# pc_afe4400_shield.net
KiCad netlist of a schematic drawn in EAGLE
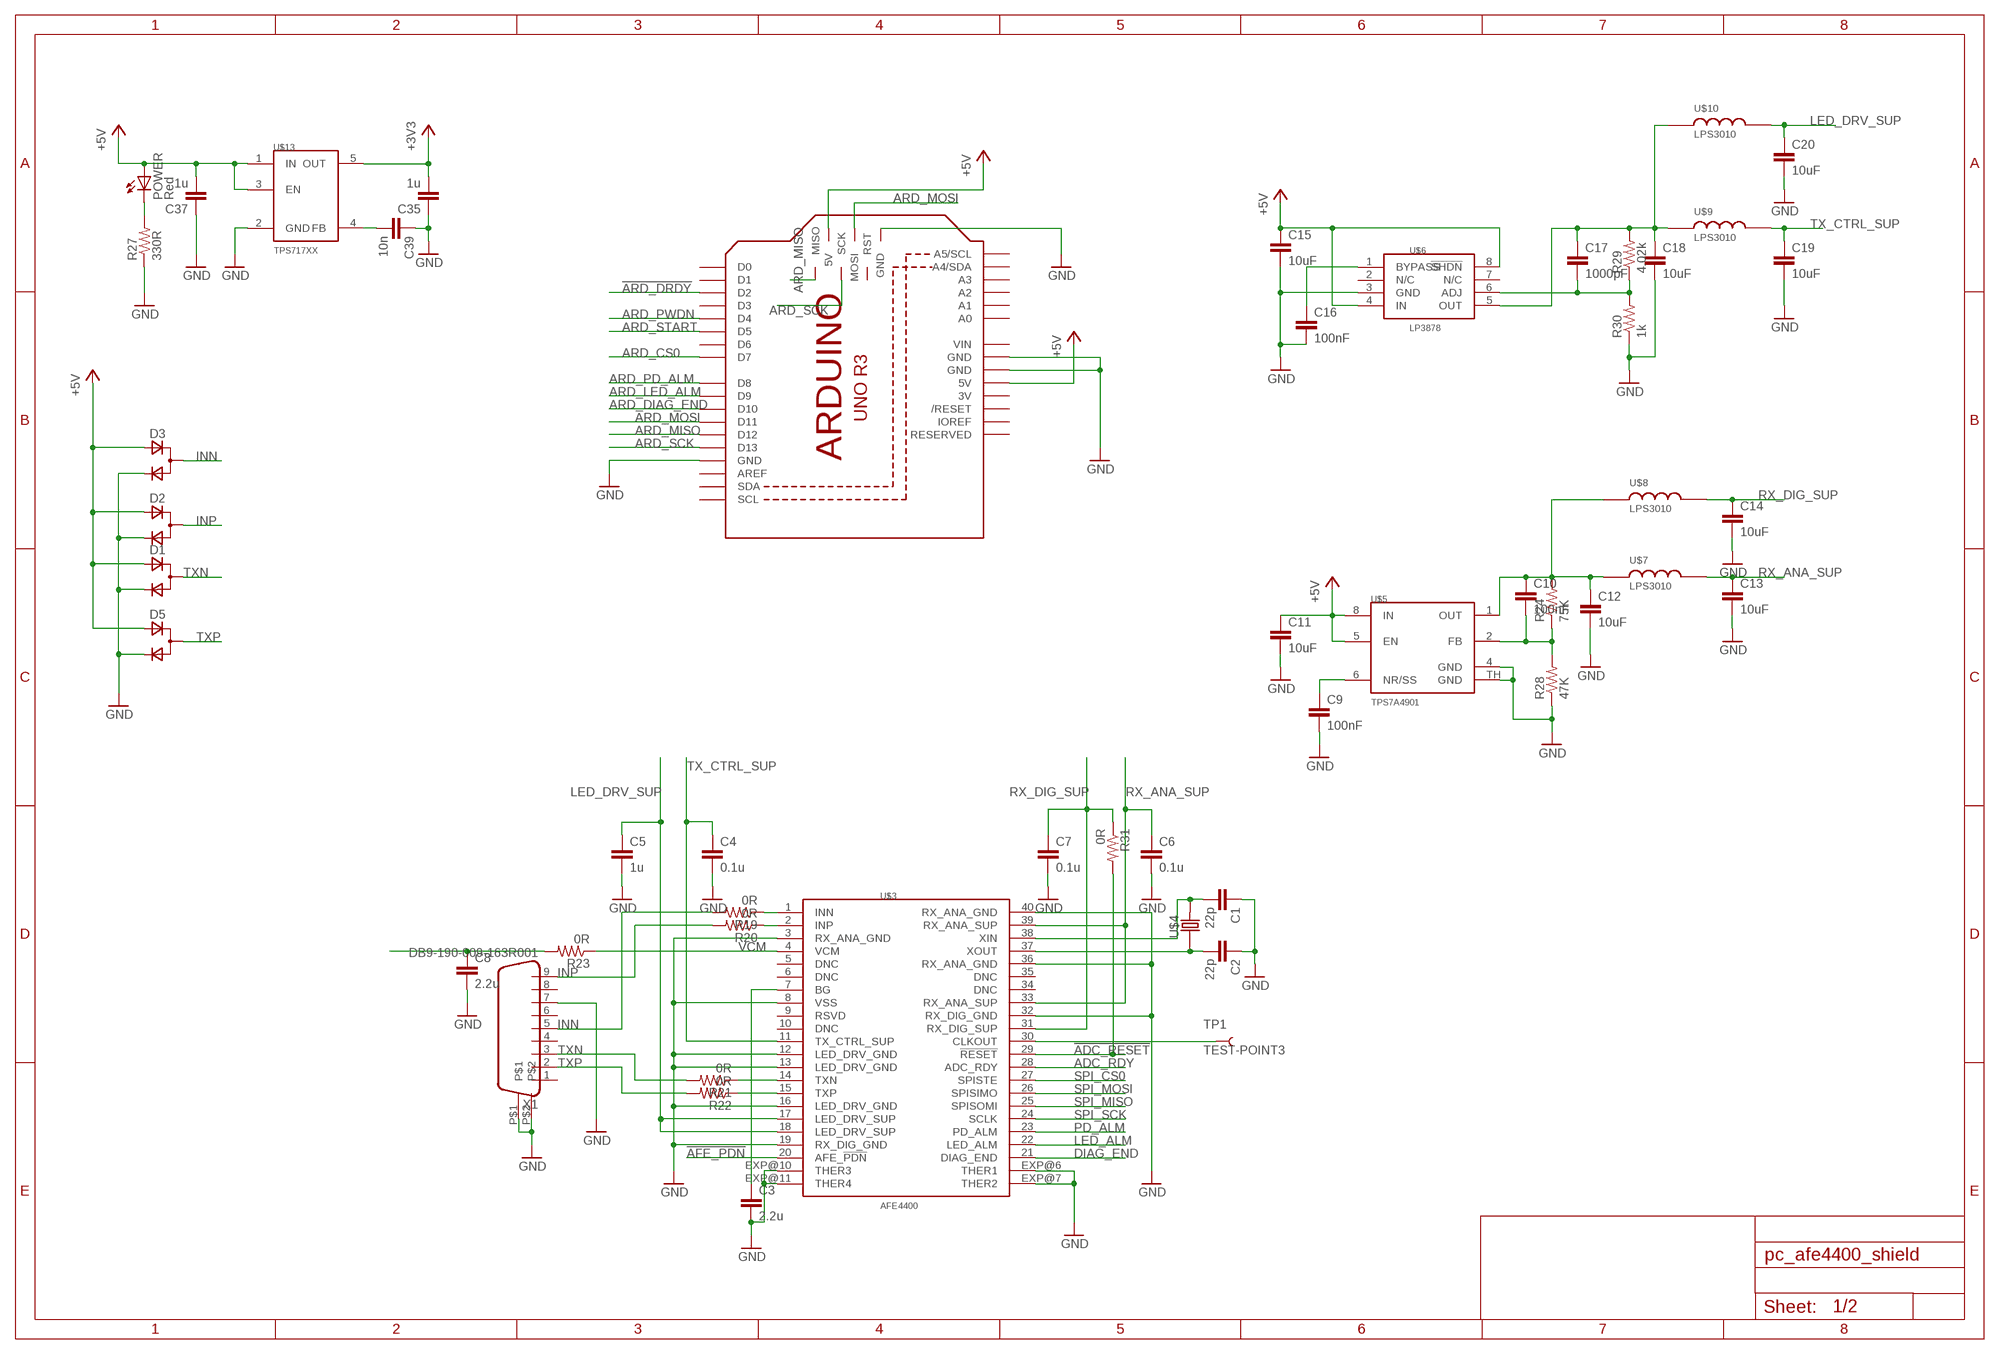
[diagram p0: schematic, sheet 1]
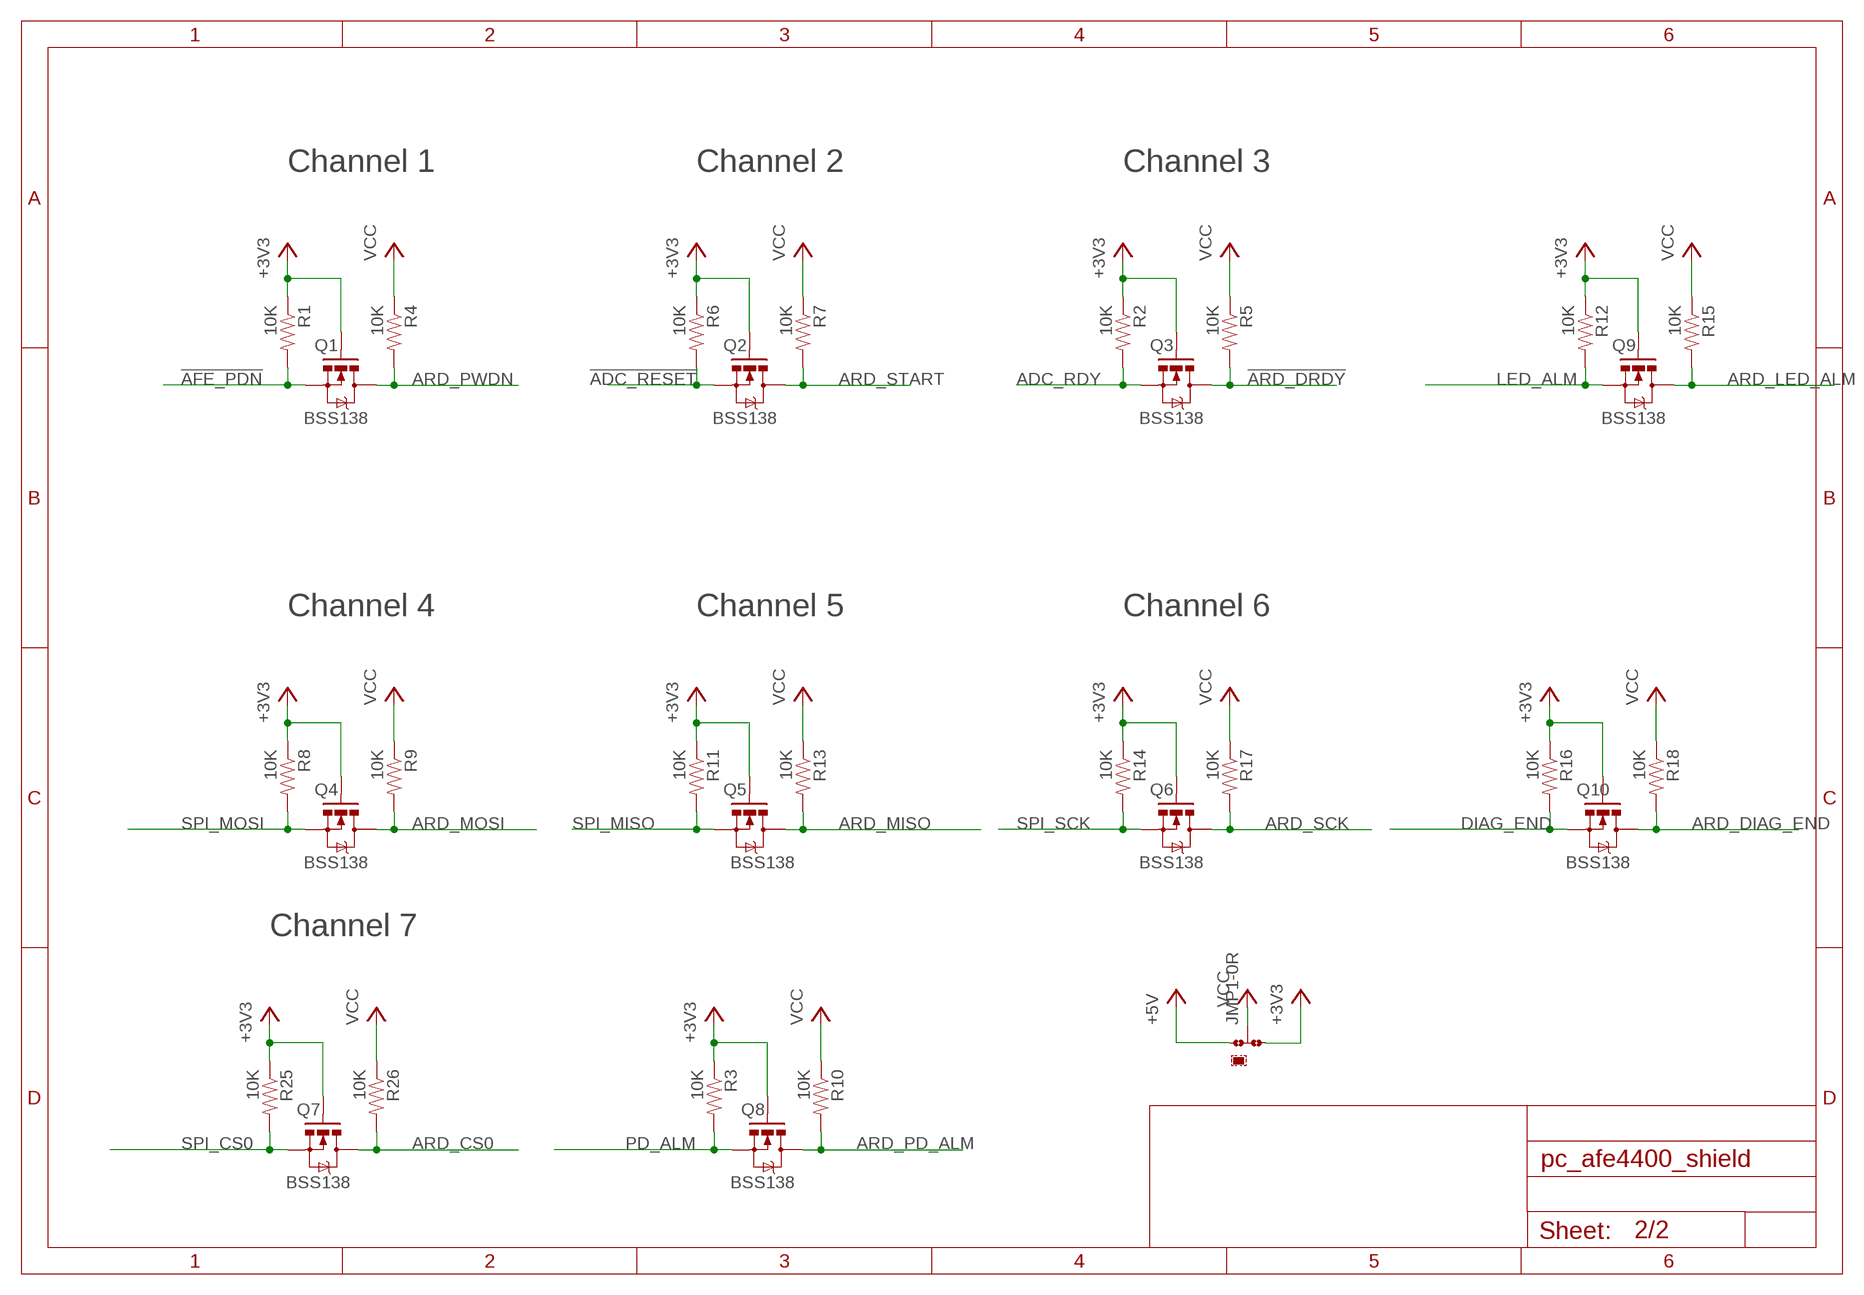
[diagram p1: schematic, sheet 2]

(export (version "E")
  (design (tool "Eeschema 10.0.6"))
  (components
    (comp (ref "JMP1")
      (value "0R-JUMPA")
      (footprint "eagle-import:A0R-JMP")
      (libsource (lib "eagle-import") (part "0R-JUMPA"))
    )
    (comp (ref "Q1")
      (value "BSS138")
      (footprint "eagle-import:SOT23-3")
      (libsource (lib "eagle-import") (part "MOSFET-NCHANNELSMD"))
    )
    (comp (ref "Q2")
      (value "BSS138")
      (footprint "eagle-import:SOT23-3")
      (libsource (lib "eagle-import") (part "MOSFET-NCHANNELSMD"))
    )
    (comp (ref "Q3")
      (value "BSS138")
      (footprint "eagle-import:SOT23-3")
      (libsource (lib "eagle-import") (part "MOSFET-NCHANNELSMD"))
    )
    (comp (ref "Q4")
      (value "BSS138")
      (footprint "eagle-import:SOT23-3")
      (libsource (lib "eagle-import") (part "MOSFET-NCHANNELSMD"))
    )
    (comp (ref "Q5")
      (value "BSS138")
      (footprint "eagle-import:SOT23-3")
      (libsource (lib "eagle-import") (part "MOSFET-NCHANNELSMD"))
    )
    (comp (ref "Q6")
      (value "BSS138")
      (footprint "eagle-import:SOT23-3")
      (libsource (lib "eagle-import") (part "MOSFET-NCHANNELSMD"))
    )
    (comp (ref "Q7")
      (value "BSS138")
      (footprint "eagle-import:SOT23-3")
      (libsource (lib "eagle-import") (part "MOSFET-NCHANNELSMD"))
    )
    (comp (ref "Q8")
      (value "BSS138")
      (footprint "eagle-import:SOT23-3")
      (libsource (lib "eagle-import") (part "MOSFET-NCHANNELSMD"))
    )
    (comp (ref "Q9")
      (value "BSS138")
      (footprint "eagle-import:SOT23-3")
      (libsource (lib "eagle-import") (part "MOSFET-NCHANNELSMD"))
    )
    (comp (ref "Q10")
      (value "BSS138")
      (footprint "eagle-import:SOT23-3")
      (libsource (lib "eagle-import") (part "MOSFET-NCHANNELSMD"))
    )
    (comp (ref "R1")
      (value "10K")
      (footprint "eagle-import:0805")
      (libsource (lib "eagle-import") (part "RESISTOR0805-RES"))
    )
    (comp (ref "R2")
      (value "10K")
      (footprint "eagle-import:0805")
      (libsource (lib "eagle-import") (part "RESISTOR0805-RES"))
    )
    (comp (ref "R3")
      (value "10K")
      (footprint "eagle-import:0805")
      (libsource (lib "eagle-import") (part "RESISTOR0805-RES"))
    )
    (comp (ref "R4")
      (value "10K")
      (footprint "eagle-import:0805")
      (libsource (lib "eagle-import") (part "RESISTOR0805-RES"))
    )
    (comp (ref "R5")
      (value "10K")
      (footprint "eagle-import:0805")
      (libsource (lib "eagle-import") (part "RESISTOR0805-RES"))
    )
    (comp (ref "R6")
      (value "10K")
      (footprint "eagle-import:0805")
      (libsource (lib "eagle-import") (part "RESISTOR0805-RES"))
    )
    (comp (ref "R7")
      (value "10K")
      (footprint "eagle-import:0805")
      (libsource (lib "eagle-import") (part "RESISTOR0805-RES"))
    )
    (comp (ref "R8")
      (value "10K")
      (footprint "eagle-import:0805")
      (libsource (lib "eagle-import") (part "RESISTOR0805-RES"))
    )
    (comp (ref "R9")
      (value "10K")
      (footprint "eagle-import:0805")
      (libsource (lib "eagle-import") (part "RESISTOR0805-RES"))
    )
    (comp (ref "R10")
      (value "10K")
      (footprint "eagle-import:0805")
      (libsource (lib "eagle-import") (part "RESISTOR0805-RES"))
    )
    (comp (ref "R11")
      (value "10K")
      (footprint "eagle-import:0805")
      (libsource (lib "eagle-import") (part "RESISTOR0805-RES"))
    )
    (comp (ref "R12")
      (value "10K")
      (footprint "eagle-import:0805")
      (libsource (lib "eagle-import") (part "RESISTOR0805-RES"))
    )
    (comp (ref "R13")
      (value "10K")
      (footprint "eagle-import:0805")
      (libsource (lib "eagle-import") (part "RESISTOR0805-RES"))
    )
    (comp (ref "R14")
      (value "10K")
      (footprint "eagle-import:0805")
      (libsource (lib "eagle-import") (part "RESISTOR0805-RES"))
    )
    (comp (ref "R15")
      (value "10K")
      (footprint "eagle-import:0805")
      (libsource (lib "eagle-import") (part "RESISTOR0805-RES"))
    )
    (comp (ref "R16")
      (value "10K")
      (footprint "eagle-import:0805")
      (libsource (lib "eagle-import") (part "RESISTOR0805-RES"))
    )
    (comp (ref "R17")
      (value "10K")
      (footprint "eagle-import:0805")
      (libsource (lib "eagle-import") (part "RESISTOR0805-RES"))
    )
    (comp (ref "R18")
      (value "10K")
      (footprint "eagle-import:0805")
      (libsource (lib "eagle-import") (part "RESISTOR0805-RES"))
    )
    (comp (ref "R25")
      (value "10K")
      (footprint "eagle-import:0805")
      (libsource (lib "eagle-import") (part "RESISTOR0805-RES"))
    )
    (comp (ref "R26")
      (value "10K")
      (footprint "eagle-import:0805")
      (libsource (lib "eagle-import") (part "RESISTOR0805-RES"))
    )
    (comp (ref "C1")
      (value "22p")
      (footprint "eagle-import:C0402")
      (libsource (lib "eagle-import") (part "C-EUC0402"))
    )
    (comp (ref "C2")
      (value "22p")
      (footprint "eagle-import:C0402")
      (libsource (lib "eagle-import") (part "C-EUC0402"))
    )
    (comp (ref "C3")
      (value "2.2u")
      (footprint "eagle-import:C0402")
      (libsource (lib "eagle-import") (part "C-EUC0402"))
    )
    (comp (ref "C4")
      (value "0.1u")
      (footprint "eagle-import:C0805")
      (libsource (lib "eagle-import") (part "C-EUC0805"))
    )
    (comp (ref "C5")
      (value "1u")
      (footprint "eagle-import:C0805")
      (libsource (lib "eagle-import") (part "C-EUC0805"))
    )
    (comp (ref "C6")
      (value "0.1u")
      (footprint "eagle-import:C0805")
      (libsource (lib "eagle-import") (part "C-EUC0805"))
    )
    (comp (ref "C7")
      (value "0.1u")
      (footprint "eagle-import:C0805")
      (libsource (lib "eagle-import") (part "C-EUC0805"))
    )
    (comp (ref "C8")
      (value "2.2u")
      (footprint "eagle-import:C0402")
      (libsource (lib "eagle-import") (part "C-EUC0402"))
    )
    (comp (ref "C9")
      (value "100nF")
      (footprint "eagle-import:C0805")
      (libsource (lib "eagle-import") (part "C-EUC0805"))
    )
    (comp (ref "C10")
      (value "100nF")
      (footprint "eagle-import:C0805")
      (libsource (lib "eagle-import") (part "C-EUC0805"))
    )
    (comp (ref "C11")
      (value "10uF")
      (footprint "eagle-import:C0805")
      (libsource (lib "eagle-import") (part "C-EUC0805"))
    )
    (comp (ref "C12")
      (value "10uF")
      (footprint "eagle-import:C0805")
      (libsource (lib "eagle-import") (part "C-EUC0805"))
    )
    (comp (ref "C13")
      (value "10uF")
      (footprint "eagle-import:C0805")
      (libsource (lib "eagle-import") (part "C-EUC0805"))
    )
    (comp (ref "C14")
      (value "10uF")
      (footprint "eagle-import:C0805")
      (libsource (lib "eagle-import") (part "C-EUC0805"))
    )
    (comp (ref "C15")
      (value "10uF")
      (footprint "eagle-import:C0805")
      (libsource (lib "eagle-import") (part "C-EUC0805"))
    )
    (comp (ref "C16")
      (value "100nF")
      (footprint "eagle-import:C0805")
      (libsource (lib "eagle-import") (part "C-EUC0805"))
    )
    (comp (ref "C17")
      (value "1000pF")
      (footprint "eagle-import:C0805")
      (libsource (lib "eagle-import") (part "C-EUC0805"))
    )
    (comp (ref "C18")
      (value "10uF")
      (footprint "eagle-import:C0805")
      (libsource (lib "eagle-import") (part "C-EUC0805"))
    )
    (comp (ref "C19")
      (value "10uF")
      (footprint "eagle-import:C0805")
      (libsource (lib "eagle-import") (part "C-EUC0805"))
    )
    (comp (ref "C20")
      (value "10uF")
      (footprint "eagle-import:C0805")
      (libsource (lib "eagle-import") (part "C-EUC0805"))
    )
    (comp (ref "C35")
      (value "1u")
      (footprint "eagle-import:C0805")
      (libsource (lib "eagle-import") (part "C-EUC0805"))
    )
    (comp (ref "C37")
      (value "1u")
      (footprint "eagle-import:C0805")
      (libsource (lib "eagle-import") (part "C-EUC0805"))
    )
    (comp (ref "C39")
      (value "10n")
      (footprint "eagle-import:C0805")
      (libsource (lib "eagle-import") (part "C-EUC0805"))
    )
    (comp (ref "D1")
      (value "D_ACACSOT323")
      (footprint "eagle-import:SOT323")
      (libsource (lib "eagle-import") (part "D_ACACSOT323"))
    )
    (comp (ref "D2")
      (value "D_ACACSOT323")
      (footprint "eagle-import:SOT323")
      (libsource (lib "eagle-import") (part "D_ACACSOT323"))
    )
    (comp (ref "D3")
      (value "D_ACACSOT323")
      (footprint "eagle-import:SOT323")
      (libsource (lib "eagle-import") (part "D_ACACSOT323"))
    )
    (comp (ref "D5")
      (value "D_ACACSOT323")
      (footprint "eagle-import:SOT323")
      (libsource (lib "eagle-import") (part "D_ACACSOT323"))
    )
    (comp (ref "M1")
      (value "ARDUINO")
      (footprint "eagle-import:ARDUINO")
      (libsource (lib "eagle-import") (part "ARDUINO"))
    )
    (comp (ref "POWER")
      (value "Red")
      (footprint "eagle-import:CHIPLED_0603")
      (libsource (lib "eagle-import") (part "LEDCHIPLED_0603"))
    )
    (comp (ref "R19")
      (value "0R")
      (footprint "eagle-import:R0402")
      (libsource (lib "eagle-import") (part "R-US_R0402"))
    )
    (comp (ref "R20")
      (value "0R")
      (footprint "eagle-import:R0402")
      (libsource (lib "eagle-import") (part "R-US_R0402"))
    )
    (comp (ref "R21")
      (value "0R")
      (footprint "eagle-import:R0805")
      (libsource (lib "eagle-import") (part "R-US_R0805"))
    )
    (comp (ref "R22")
      (value "0R")
      (footprint "eagle-import:R0805")
      (libsource (lib "eagle-import") (part "R-US_R0805"))
    )
    (comp (ref "R23")
      (value "0R")
      (footprint "eagle-import:R0402")
      (libsource (lib "eagle-import") (part "R-US_R0402"))
    )
    (comp (ref "R24")
      (value "75K")
      (footprint "eagle-import:R0805")
      (libsource (lib "eagle-import") (part "R-US_R0805"))
    )
    (comp (ref "R27")
      (value "330R")
      (footprint "eagle-import:R0805")
      (libsource (lib "eagle-import") (part "R-US_R0805"))
    )
    (comp (ref "R28")
      (value "47K")
      (footprint "eagle-import:R0805")
      (libsource (lib "eagle-import") (part "R-US_R0805"))
    )
    (comp (ref "R29")
      (value "4.02k")
      (footprint "eagle-import:R0805")
      (libsource (lib "eagle-import") (part "R-US_R0805"))
    )
    (comp (ref "R30")
      (value "1k")
      (footprint "eagle-import:R0805")
      (libsource (lib "eagle-import") (part "R-US_R0805"))
    )
    (comp (ref "R31")
      (value "0R")
      (footprint "eagle-import:R0805")
      (libsource (lib "eagle-import") (part "R-US_R0805"))
    )
    (comp (ref "TP1")
      (value "TEST-POINT3")
      (footprint "eagle-import:PAD.03X.03")
      (libsource (lib "eagle-import") (part "TEST-POINT3"))
    )
    (comp (ref "U$3")
      (value "AFE4400")
      (footprint "eagle-import:QFN-40")
      (libsource (lib "eagle-import") (part "AFE4400"))
    )
    (comp (ref "U$4")
      (value "ABM3")
      (footprint "eagle-import:ABM3")
      (libsource (lib "eagle-import") (part "ABM3"))
    )
    (comp (ref "U$5")
      (value "TPS7A4901")
      (footprint "eagle-import:S-PDSO-G08")
      (libsource (lib "eagle-import") (part "TPS7A4901"))
    )
    (comp (ref "U$6")
      (value "LP3878")
      (footprint "eagle-import:DDA")
      (libsource (lib "eagle-import") (part "LP3878"))
    )
    (comp (ref "U$7")
      (value "LPS3010")
      (footprint "eagle-import:LPS")
      (libsource (lib "eagle-import") (part "LPS"))
    )
    (comp (ref "U$8")
      (value "LPS3010")
      (footprint "eagle-import:LPS")
      (libsource (lib "eagle-import") (part "LPS"))
    )
    (comp (ref "U$9")
      (value "LPS3010")
      (footprint "eagle-import:LPS")
      (libsource (lib "eagle-import") (part "LPS"))
    )
    (comp (ref "U$10")
      (value "LPS3010")
      (footprint "eagle-import:LPS")
      (libsource (lib "eagle-import") (part "LPS"))
    )
    (comp (ref "U$13")
      (value "TPS717XX")
      (footprint "eagle-import:SC70-5")
      (libsource (lib "eagle-import") (part "TPS717XX"))
    )
    (comp (ref "X1")
      (value "DB9-190-009-163R001")
      (footprint "eagle-import:DB9-190-009-163R001")
      (libsource (lib "eagle-import") (part "DB9-190-009-163R001"))
    )
  )
  (nets
    (net (code "1") (name "+3V3") (class "Default")
      (node (ref "C35") (pin "2") (pinfunction "2_2") (pintype "passive"))
      (node (ref "JMP1") (pin "3") (pinfunction "3_3") (pintype "passive"))
      (node (ref "Q1") (pin "1") (pinfunction "G_1") (pintype "passive"))
      (node (ref "Q10") (pin "1") (pinfunction "G_1") (pintype "passive"))
      (node (ref "Q2") (pin "1") (pinfunction "G_1") (pintype "passive"))
      (node (ref "Q3") (pin "1") (pinfunction "G_1") (pintype "passive"))
      (node (ref "Q4") (pin "1") (pinfunction "G_1") (pintype "passive"))
      (node (ref "Q5") (pin "1") (pinfunction "G_1") (pintype "passive"))
      (node (ref "Q6") (pin "1") (pinfunction "G_1") (pintype "passive"))
      (node (ref "Q7") (pin "1") (pinfunction "G_1") (pintype "passive"))
      (node (ref "Q8") (pin "1") (pinfunction "G_1") (pintype "passive"))
      (node (ref "Q9") (pin "1") (pinfunction "G_1") (pintype "passive"))
      (node (ref "R1") (pin "1") (pinfunction "1_1") (pintype "passive"))
      (node (ref "R11") (pin "1") (pinfunction "1_1") (pintype "passive"))
      (node (ref "R12") (pin "1") (pinfunction "1_1") (pintype "passive"))
      (node (ref "R14") (pin "1") (pinfunction "1_1") (pintype "passive"))
      (node (ref "R16") (pin "1") (pinfunction "1_1") (pintype "passive"))
      (node (ref "R2") (pin "1") (pinfunction "1_1") (pintype "passive"))
      (node (ref "R25") (pin "1") (pinfunction "1_1") (pintype "passive"))
      (node (ref "R3") (pin "1") (pinfunction "1_1") (pintype "passive"))
      (node (ref "R6") (pin "1") (pinfunction "1_1") (pintype "passive"))
      (node (ref "R8") (pin "1") (pinfunction "1_1") (pintype "passive"))
      (node (ref "U$13") (pin "5") (pinfunction "OUT_5") (pintype "bidirectional"))
    )
    (net (code "2") (name "+5V") (class "Default")
      (node (ref "C11") (pin "1") (pinfunction "1_1") (pintype "passive"))
      (node (ref "C15") (pin "1") (pinfunction "1_1") (pintype "passive"))
      (node (ref "C37") (pin "2") (pinfunction "2_2") (pintype "passive"))
      (node (ref "D1") (pin "3") (pinfunction "A_3") (pintype "passive"))
      (node (ref "D2") (pin "3") (pinfunction "A_3") (pintype "passive"))
      (node (ref "D3") (pin "3") (pinfunction "A_3") (pintype "passive"))
      (node (ref "D5") (pin "3") (pinfunction "A_3") (pintype "passive"))
      (node (ref "JMP1") (pin "1") (pinfunction "1_1") (pintype "passive"))
      (node (ref "M1") (pin "5V") (pinfunction "5V_5V") (pintype "power_in"))
      (node (ref "M1") (pin "5V_ICSP") (pinfunction "5V_5V_ICSP") (pintype "passive"))
      (node (ref "POWER") (pin "A") (pinfunction "A_A") (pintype "passive"))
      (node (ref "U$13") (pin "1") (pinfunction "IN_1") (pintype "bidirectional"))
      (node (ref "U$13") (pin "3") (pinfunction "EN_3") (pintype "bidirectional"))
      (node (ref "U$5") (pin "5") (pinfunction "EN_5") (pintype "bidirectional"))
      (node (ref "U$5") (pin "8") (pinfunction "IN_8") (pintype "bidirectional"))
      (node (ref "U$6") (pin "4") (pinfunction "IN_4") (pintype "bidirectional"))
      (node (ref "U$6") (pin "8") (pinfunction "~{SHDN}_8") (pintype "bidirectional"))
    )
    (net (code "3") (name "3V") (class "Default")
      (node (ref "M1") (pin "3V") (pinfunction "3V_3V") (pintype "power_in"))
    )
    (net (code "4") (name "ADC_RDY") (class "Default")
      (node (ref "Q3") (pin "2") (pinfunction "S_2") (pintype "passive"))
      (node (ref "R2") (pin "2") (pinfunction "2_2") (pintype "passive"))
      (node (ref "U$3") (pin "28") (pinfunction "ADC_RDY_28") (pintype "bidirectional"))
    )
    (net (code "5") (name "ARD_CS0") (class "Default")
      (node (ref "M1") (pin "D7") (pinfunction "D7_D7") (pintype "bidirectional"))
      (node (ref "Q7") (pin "3") (pinfunction "D_3") (pintype "passive"))
      (node (ref "R26") (pin "2") (pinfunction "2_2") (pintype "passive"))
    )
    (net (code "6") (name "ARD_DIAG_END") (class "Default")
      (node (ref "M1") (pin "D10") (pinfunction "D10_D10") (pintype "bidirectional"))
      (node (ref "Q10") (pin "3") (pinfunction "D_3") (pintype "passive"))
      (node (ref "R18") (pin "2") (pinfunction "2_2") (pintype "passive"))
    )
    (net (code "7") (name "ARD_LED_ALM") (class "Default")
      (node (ref "M1") (pin "D9") (pinfunction "D9_D9") (pintype "bidirectional"))
      (node (ref "Q9") (pin "3") (pinfunction "D_3") (pintype "passive"))
      (node (ref "R15") (pin "2") (pinfunction "2_2") (pintype "passive"))
    )
    (net (code "8") (name "ARD_MISO") (class "Default")
      (node (ref "M1") (pin "D12") (pinfunction "D12_D12") (pintype "bidirectional"))
      (node (ref "M1") (pin "MISO") (pinfunction "MISO_MISO") (pintype "passive"))
      (node (ref "Q5") (pin "3") (pinfunction "D_3") (pintype "passive"))
      (node (ref "R13") (pin "2") (pinfunction "2_2") (pintype "passive"))
    )
    (net (code "9") (name "ARD_MOSI") (class "Default")
      (node (ref "M1") (pin "D11") (pinfunction "D11_D11") (pintype "bidirectional"))
      (node (ref "M1") (pin "MOSI") (pinfunction "MOSI_MOSI") (pintype "passive"))
      (node (ref "Q4") (pin "3") (pinfunction "D_3") (pintype "passive"))
      (node (ref "R9") (pin "2") (pinfunction "2_2") (pintype "passive"))
    )
    (net (code "10") (name "ARD_PD_ALM") (class "Default")
      (node (ref "M1") (pin "D8") (pinfunction "D8_D8") (pintype "bidirectional"))
      (node (ref "Q8") (pin "3") (pinfunction "D_3") (pintype "passive"))
      (node (ref "R10") (pin "2") (pinfunction "2_2") (pintype "passive"))
    )
    (net (code "11") (name "ARD_PWDN") (class "Default")
      (node (ref "M1") (pin "D4") (pinfunction "D4_D4") (pintype "bidirectional"))
      (node (ref "Q1") (pin "3") (pinfunction "D_3") (pintype "passive"))
      (node (ref "R4") (pin "2") (pinfunction "2_2") (pintype "passive"))
    )
    (net (code "12") (name "ARD_SCK") (class "Default")
      (node (ref "M1") (pin "D13") (pinfunction "D13_D13") (pintype "bidirectional"))
      (node (ref "M1") (pin "SCK") (pinfunction "SCK_SCK") (pintype "passive"))
      (node (ref "Q6") (pin "3") (pinfunction "D_3") (pintype "passive"))
      (node (ref "R17") (pin "2") (pinfunction "2_2") (pintype "passive"))
    )
    (net (code "13") (name "ARD_START") (class "Default")
      (node (ref "M1") (pin "D5") (pinfunction "D5_D5") (pintype "bidirectional"))
      (node (ref "Q2") (pin "3") (pinfunction "D_3") (pintype "passive"))
      (node (ref "R7") (pin "2") (pinfunction "2_2") (pintype "passive"))
    )
    (net (code "14") (name "DIAG_END") (class "Default")
      (node (ref "Q10") (pin "2") (pinfunction "S_2") (pintype "passive"))
      (node (ref "R16") (pin "2") (pinfunction "2_2") (pintype "passive"))
      (node (ref "U$3") (pin "21") (pinfunction "DIAG_END_21") (pintype "bidirectional"))
    )
    (net (code "15") (name "GND") (class "Default")
      (node (ref "C1") (pin "1") (pinfunction "1_1") (pintype "passive"))
      (node (ref "C11") (pin "2") (pinfunction "2_2") (pintype "passive"))
      (node (ref "C12") (pin "2") (pinfunction "2_2") (pintype "passive"))
      (node (ref "C13") (pin "2") (pinfunction "2_2") (pintype "passive"))
      (node (ref "C14") (pin "2") (pinfunction "2_2") (pintype "passive"))
      (node (ref "C15") (pin "2") (pinfunction "2_2") (pintype "passive"))
      (node (ref "C16") (pin "2") (pinfunction "2_2") (pintype "passive"))
      (node (ref "C18") (pin "2") (pinfunction "2_2") (pintype "passive"))
      (node (ref "C19") (pin "2") (pinfunction "2_2") (pintype "passive"))
      (node (ref "C2") (pin "1") (pinfunction "1_1") (pintype "passive"))
      (node (ref "C20") (pin "2") (pinfunction "2_2") (pintype "passive"))
      (node (ref "C3") (pin "2") (pinfunction "2_2") (pintype "passive"))
      (node (ref "C35") (pin "1") (pinfunction "1_1") (pintype "passive"))
      (node (ref "C37") (pin "1") (pinfunction "1_1") (pintype "passive"))
      (node (ref "C39") (pin "1") (pinfunction "1_1") (pintype "passive"))
      (node (ref "C4") (pin "2") (pinfunction "2_2") (pintype "passive"))
      (node (ref "C5") (pin "2") (pinfunction "2_2") (pintype "passive"))
      (node (ref "C6") (pin "2") (pinfunction "2_2") (pintype "passive"))
      (node (ref "C7") (pin "2") (pinfunction "2_2") (pintype "passive"))
      (node (ref "C8") (pin "2") (pinfunction "2_2") (pintype "passive"))
      (node (ref "C9") (pin "2") (pinfunction "2_2") (pintype "passive"))
      (node (ref "D1") (pin "2") (pinfunction "C_2") (pintype "passive"))
      (node (ref "D2") (pin "2") (pinfunction "C_2") (pintype "passive"))
      (node (ref "D3") (pin "2") (pinfunction "C_2") (pintype "passive"))
      (node (ref "D5") (pin "2") (pinfunction "C_2") (pintype "passive"))
      (node (ref "M1") (pin "GND") (pinfunction "GND_GND") (pintype "power_in"))
      (node (ref "M1") (pin "GND@1") (pinfunction "GND_GND@1") (pintype "power_in"))
      (node (ref "M1") (pin "GND@2") (pinfunction "GND_GND@2") (pintype "power_in"))
      (node (ref "M1") (pin "GND@3") (pinfunction "GND_GND@3") (pintype "passive"))
      (node (ref "R27") (pin "1") (pinfunction "1_1") (pintype "passive"))
      (node (ref "R28") (pin "1") (pinfunction "1_1") (pintype "passive"))
      (node (ref "R30") (pin "1") (pinfunction "1_1") (pintype "passive"))
      (node (ref "U$13") (pin "2") (pinfunction "GND_2") (pintype "bidirectional"))
      (node (ref "U$3") (pin "12") (pinfunction "LED_DRV_GND_12") (pintype "bidirectional"))
      (node (ref "U$3") (pin "13") (pinfunction "LED_DRV_GND_13") (pintype "bidirectional"))
      (node (ref "U$3") (pin "16") (pinfunction "LED_DRV_GND_16") (pintype "bidirectional"))
      (node (ref "U$3") (pin "19") (pinfunction "RX_DIG_GND_19") (pintype "bidirectional"))
      (node (ref "U$3") (pin "3") (pinfunction "RX_ANA_GND_3") (pintype "bidirectional"))
      (node (ref "U$3") (pin "32") (pinfunction "RX_DIG_GND_32") (pintype "bidirectional"))
      (node (ref "U$3") (pin "36") (pinfunction "RX_ANA_GND_36") (pintype "bidirectional"))
      (node (ref "U$3") (pin "40") (pinfunction "RX_ANA_GND_40") (pintype "bidirectional"))
      (node (ref "U$3") (pin "8") (pinfunction "VSS_8") (pintype "bidirectional"))
      (node (ref "U$3") (pin "EXP@10") (pinfunction "THER3_EXP@10") (pintype "bidirectional"))
      (node (ref "U$3") (pin "EXP@11") (pinfunction "THER4_EXP@11") (pintype "bidirectional"))
      (node (ref "U$3") (pin "EXP@6") (pinfunction "THER1_EXP@6") (pintype "bidirectional"))
      (node (ref "U$3") (pin "EXP@7") (pinfunction "THER2_EXP@7") (pintype "bidirectional"))
      (node (ref "U$5") (pin "4") (pinfunction "GND_4") (pintype "bidirectional"))
      (node (ref "U$5") (pin "TH") (pinfunction "GND_TH") (pintype "bidirectional"))
      (node (ref "U$6") (pin "3") (pinfunction "GND_3") (pintype "bidirectional"))
      (node (ref "X1") (pin "7") (pinfunction "7_7") (pintype "passive"))
      (node (ref "X1") (pin "P$1") (pinfunction "P$1_P$1") (pintype "bidirectional"))
      (node (ref "X1") (pin "P$2") (pinfunction "P$2_P$2") (pintype "bidirectional"))
    )
    (net (code "16") (name "INN") (class "Default")
      (node (ref "D3") (pin "1") (pinfunction "CA_1") (pintype "passive"))
      (node (ref "R19") (pin "2") (pinfunction "2_2") (pintype "passive"))
      (node (ref "X1") (pin "5") (pinfunction "5_5") (pintype "passive"))
    )
    (net (code "17") (name "INP") (class "Default")
      (node (ref "D2") (pin "1") (pinfunction "CA_1") (pintype "passive"))
      (node (ref "R20") (pin "2") (pinfunction "2_2") (pintype "passive"))
      (node (ref "X1") (pin "9") (pinfunction "9_9") (pintype "passive"))
    )
    (net (code "18") (name "LED_ALM") (class "Default")
      (node (ref "Q9") (pin "2") (pinfunction "S_2") (pintype "passive"))
      (node (ref "R12") (pin "2") (pinfunction "2_2") (pintype "passive"))
      (node (ref "U$3") (pin "22") (pinfunction "LED_ALM_22") (pintype "bidirectional"))
    )
    (net (code "19") (name "LED_DRV_SUP") (class "Default")
      (node (ref "C20") (pin "1") (pinfunction "1_1") (pintype "passive"))
      (node (ref "C5") (pin "1") (pinfunction "1_1") (pintype "passive"))
      (node (ref "U$10") (pin "2") (pinfunction "P$2_2") (pintype "bidirectional"))
      (node (ref "U$3") (pin "17") (pinfunction "LED_DRV_SUP_17") (pintype "bidirectional"))
      (node (ref "U$3") (pin "18") (pinfunction "LED_DRV_SUP_18") (pintype "bidirectional"))
    )
    (net (code "20") (name "Net-(C8-Pad1)") (class "Default")
      (node (ref "C8") (pin "1") (pinfunction "1_1") (pintype "passive"))
      (node (ref "R23") (pin "2") (pinfunction "2_2") (pintype "passive"))
    )
    (net (code "21") (name "Net-(POWER-PadC)") (class "Default")
      (node (ref "POWER") (pin "C") (pinfunction "C_C") (pintype "passive"))
      (node (ref "R27") (pin "2") (pinfunction "2_2") (pintype "passive"))
    )
    (net (code "22") (name "Net-(TP1-1)") (class "Default")
      (node (ref "TP1") (pin "P$1") (pinfunction "1_P$1") (pintype "bidirectional"))
      (node (ref "U$3") (pin "30") (pinfunction "CLKOUT_30") (pintype "bidirectional"))
    )
    (net (code "23") (name "Net-(U$3-BG)") (class "Default")
      (node (ref "C3") (pin "1") (pinfunction "1_1") (pintype "passive"))
      (node (ref "U$3") (pin "7") (pinfunction "BG_7") (pintype "bidirectional"))
    )
    (net (code "24") (name "Net-(U$3-INN)") (class "Default")
      (node (ref "R19") (pin "1") (pinfunction "1_1") (pintype "passive"))
      (node (ref "U$3") (pin "1") (pinfunction "INN_1") (pintype "bidirectional"))
    )
    (net (code "25") (name "Net-(U$3-INP)") (class "Default")
      (node (ref "R20") (pin "1") (pinfunction "1_1") (pintype "passive"))
      (node (ref "U$3") (pin "2") (pinfunction "INP_2") (pintype "bidirectional"))
    )
    (net (code "26") (name "Net-(U$3-TXN)") (class "Default")
      (node (ref "R21") (pin "1") (pinfunction "1_1") (pintype "passive"))
      (node (ref "U$3") (pin "14") (pinfunction "TXN_14") (pintype "bidirectional"))
    )
    (net (code "27") (name "Net-(U$3-TXP)") (class "Default")
      (node (ref "R22") (pin "1") (pinfunction "1_1") (pintype "passive"))
      (node (ref "U$3") (pin "15") (pinfunction "TXP_15") (pintype "bidirectional"))
    )
    (net (code "28") (name "Net-(U$3-XIN)") (class "Default")
      (node (ref "C1") (pin "2") (pinfunction "2_2") (pintype "passive"))
      (node (ref "U$3") (pin "38") (pinfunction "XIN_38") (pintype "bidirectional"))
      (node (ref "U$4") (pin "2") (pinfunction "2_2") (pintype "passive"))
    )
    (net (code "29") (name "Net-(U$3-XOUT)") (class "Default")
      (node (ref "C2") (pin "2") (pinfunction "2_2") (pintype "passive"))
      (node (ref "U$3") (pin "37") (pinfunction "XOUT_37") (pintype "bidirectional"))
      (node (ref "U$4") (pin "1") (pinfunction "1_1") (pintype "passive"))
    )
    (net (code "30") (name "Net-(U$5-FB)") (class "Default")
      (node (ref "C10") (pin "2") (pinfunction "2_2") (pintype "passive"))
      (node (ref "R24") (pin "1") (pinfunction "1_1") (pintype "passive"))
      (node (ref "R28") (pin "2") (pinfunction "2_2") (pintype "passive"))
      (node (ref "U$5") (pin "2") (pinfunction "FB_2") (pintype "bidirectional"))
    )
    (net (code "31") (name "Net-(U$5-NR{slash}SS)") (class "Default")
      (node (ref "C9") (pin "1") (pinfunction "1_1") (pintype "passive"))
      (node (ref "U$5") (pin "6") (pinfunction "NR/SS_6") (pintype "bidirectional"))
    )
    (net (code "32") (name "Net-(U$5-OUT)") (class "Default")
      (node (ref "C10") (pin "1") (pinfunction "1_1") (pintype "passive"))
      (node (ref "C12") (pin "1") (pinfunction "1_1") (pintype "passive"))
      (node (ref "R24") (pin "2") (pinfunction "2_2") (pintype "passive"))
      (node (ref "U$5") (pin "1") (pinfunction "OUT_1") (pintype "bidirectional"))
      (node (ref "U$7") (pin "1") (pinfunction "P$1_1") (pintype "bidirectional"))
      (node (ref "U$8") (pin "1") (pinfunction "P$1_1") (pintype "bidirectional"))
    )
    (net (code "33") (name "Net-(U$6-ADJ)") (class "Default")
      (node (ref "C17") (pin "2") (pinfunction "2_2") (pintype "passive"))
      (node (ref "R29") (pin "1") (pinfunction "1_1") (pintype "passive"))
      (node (ref "R30") (pin "2") (pinfunction "2_2") (pintype "passive"))
      (node (ref "U$6") (pin "6") (pinfunction "ADJ_6") (pintype "bidirectional"))
    )
    (net (code "34") (name "Net-(U$6-BYPASS)") (class "Default")
      (node (ref "C16") (pin "1") (pinfunction "1_1") (pintype "passive"))
      (node (ref "U$6") (pin "1") (pinfunction "BYPASS_1") (pintype "bidirectional"))
    )
    (net (code "35") (name "Net-(U$10-P$1)") (class "Default")
      (node (ref "C17") (pin "1") (pinfunction "1_1") (pintype "passive"))
      (node (ref "C18") (pin "1") (pinfunction "1_1") (pintype "passive"))
      (node (ref "R29") (pin "2") (pinfunction "2_2") (pintype "passive"))
      (node (ref "U$10") (pin "1") (pinfunction "P$1_1") (pintype "bidirectional"))
      (node (ref "U$6") (pin "5") (pinfunction "OUT_5") (pintype "bidirectional"))
      (node (ref "U$9") (pin "1") (pinfunction "P$1_1") (pintype "bidirectional"))
    )
    (net (code "36") (name "Net-(U$13-FB)") (class "Default")
      (node (ref "C39") (pin "2") (pinfunction "2_2") (pintype "passive"))
      (node (ref "U$13") (pin "4") (pinfunction "FB_4") (pintype "bidirectional"))
    )
    (net (code "37") (name "PD_ALM") (class "Default")
      (node (ref "Q8") (pin "2") (pinfunction "S_2") (pintype "passive"))
      (node (ref "R3") (pin "2") (pinfunction "2_2") (pintype "passive"))
      (node (ref "U$3") (pin "23") (pinfunction "PD_ALM_23") (pintype "bidirectional"))
    )
    (net (code "38") (name "RX_ANA_SUP") (class "Default")
      (node (ref "C13") (pin "1") (pinfunction "1_1") (pintype "passive"))
      (node (ref "C6") (pin "1") (pinfunction "1_1") (pintype "passive"))
      (node (ref "U$3") (pin "33") (pinfunction "RX_ANA_SUP_33") (pintype "bidirectional"))
      (node (ref "U$3") (pin "39") (pinfunction "RX_ANA_SUP_39") (pintype "bidirectional"))
      (node (ref "U$7") (pin "2") (pinfunction "P$2_2") (pintype "bidirectional"))
    )
    (net (code "39") (name "RX_DIG_SUP") (class "Default")
      (node (ref "C14") (pin "1") (pinfunction "1_1") (pintype "passive"))
      (node (ref "C7") (pin "1") (pinfunction "1_1") (pintype "passive"))
      (node (ref "R31") (pin "1") (pinfunction "1_1") (pintype "passive"))
      (node (ref "U$3") (pin "31") (pinfunction "RX_DIG_SUP_31") (pintype "bidirectional"))
      (node (ref "U$8") (pin "2") (pinfunction "P$2_2") (pintype "bidirectional"))
    )
    (net (code "40") (name "SPI_CS0") (class "Default")
      (node (ref "Q7") (pin "2") (pinfunction "S_2") (pintype "passive"))
      (node (ref "R25") (pin "2") (pinfunction "2_2") (pintype "passive"))
      (node (ref "U$3") (pin "27") (pinfunction "SPISTE_27") (pintype "bidirectional"))
    )
    (net (code "41") (name "SPI_MISO") (class "Default")
      (node (ref "Q5") (pin "2") (pinfunction "S_2") (pintype "passive"))
      (node (ref "R11") (pin "2") (pinfunction "2_2") (pintype "passive"))
      (node (ref "U$3") (pin "25") (pinfunction "SPISOMI_25") (pintype "bidirectional"))
    )
    (net (code "42") (name "SPI_MOSI") (class "Default")
      (node (ref "Q4") (pin "2") (pinfunction "S_2") (pintype "passive"))
      (node (ref "R8") (pin "2") (pinfunction "2_2") (pintype "passive"))
      (node (ref "U$3") (pin "26") (pinfunction "SPISIMO_26") (pintype "bidirectional"))
    )
    (net (code "43") (name "SPI_SCK") (class "Default")
      (node (ref "Q6") (pin "2") (pinfunction "S_2") (pintype "passive"))
      (node (ref "R14") (pin "2") (pinfunction "2_2") (pintype "passive"))
      (node (ref "U$3") (pin "24") (pinfunction "SCLK_24") (pintype "bidirectional"))
    )
    (net (code "44") (name "TXN") (class "Default")
      (node (ref "D1") (pin "1") (pinfunction "CA_1") (pintype "passive"))
      (node (ref "R21") (pin "2") (pinfunction "2_2") (pintype "passive"))
      (node (ref "X1") (pin "3") (pinfunction "3_3") (pintype "passive"))
    )
    (net (code "45") (name "TXP") (class "Default")
      (node (ref "D5") (pin "1") (pinfunction "CA_1") (pintype "passive"))
      (node (ref "R22") (pin "2") (pinfunction "2_2") (pintype "passive"))
      (node (ref "X1") (pin "2") (pinfunction "2_2") (pintype "passive"))
    )
    (net (code "46") (name "TX_CTRL_SUP") (class "Default")
      (node (ref "C19") (pin "1") (pinfunction "1_1") (pintype "passive"))
      (node (ref "C4") (pin "1") (pinfunction "1_1") (pintype "passive"))
      (node (ref "U$3") (pin "11") (pinfunction "TX_CTRL_SUP_11") (pintype "bidirectional"))
      (node (ref "U$9") (pin "2") (pinfunction "P$2_2") (pintype "bidirectional"))
    )
    (net (code "47") (name "VCC") (class "Default")
      (node (ref "JMP1") (pin "2") (pinfunction "2_2") (pintype "passive"))
      (node (ref "R10") (pin "1") (pinfunction "1_1") (pintype "passive"))
      (node (ref "R13") (pin "1") (pinfunction "1_1") (pintype "passive"))
      (node (ref "R15") (pin "1") (pinfunction "1_1") (pintype "passive"))
      (node (ref "R17") (pin "1") (pinfunction "1_1") (pintype "passive"))
      (node (ref "R18") (pin "1") (pinfunction "1_1") (pintype "passive"))
      (node (ref "R26") (pin "1") (pinfunction "1_1") (pintype "passive"))
      (node (ref "R4") (pin "1") (pinfunction "1_1") (pintype "passive"))
      (node (ref "R5") (pin "1") (pinfunction "1_1") (pintype "passive"))
      (node (ref "R7") (pin "1") (pinfunction "1_1") (pintype "passive"))
      (node (ref "R9") (pin "1") (pinfunction "1_1") (pintype "passive"))
    )
    (net (code "48") (name "VCM") (class "Default")
      (node (ref "R23") (pin "1") (pinfunction "1_1") (pintype "passive"))
      (node (ref "U$3") (pin "4") (pinfunction "VCM_4") (pintype "bidirectional"))
    )
    (net (code "49") (name "VIN") (class "Default")
      (node (ref "M1") (pin "VIN") (pinfunction "VIN_VIN") (pintype "power_in"))
    )
    (net (code "50") (name "unconnected-(M1-A4{slash}SDA-PadA4)") (class "Default")
      (node (ref "M1") (pin "A4") (pinfunction "A4/SDA_A4") (pintype "bidirectional"))
    )
    (net (code "51") (name "unconnected-(M1-A5{slash}SCL-PadA5)") (class "Default")
      (node (ref "M1") (pin "A5") (pinfunction "A5/SCL_A5") (pintype "bidirectional"))
    )
    (net (code "52") (name "unconnected-(M1-PadA0)") (class "Default")
      (node (ref "M1") (pin "A0") (pinfunction "A0_A0") (pintype "bidirectional"))
    )
    (net (code "53") (name "unconnected-(M1-PadA1)") (class "Default")
      (node (ref "M1") (pin "A1") (pinfunction "A1_A1") (pintype "bidirectional"))
    )
    (net (code "54") (name "unconnected-(M1-PadA2)") (class "Default")
      (node (ref "M1") (pin "A2") (pinfunction "A2_A2") (pintype "bidirectional"))
    )
    (net (code "55") (name "unconnected-(M1-PadA3)") (class "Default")
      (node (ref "M1") (pin "A3") (pinfunction "A3_A3") (pintype "bidirectional"))
    )
    (net (code "56") (name "unconnected-(M1-PadAREF)") (class "Default")
      (node (ref "M1") (pin "AREF") (pinfunction "AREF_AREF") (pintype "bidirectional"))
    )
    (net (code "57") (name "unconnected-(M1-PadD0)") (class "Default")
      (node (ref "M1") (pin "D0") (pinfunction "D0_D0") (pintype "bidirectional"))
    )
    (net (code "58") (name "unconnected-(M1-PadD1)") (class "Default")
      (node (ref "M1") (pin "D1") (pinfunction "D1_D1") (pintype "bidirectional"))
    )
    (net (code "59") (name "unconnected-(M1-PadD3)") (class "Default")
      (node (ref "M1") (pin "D3") (pinfunction "D3_D3") (pintype "bidirectional"))
    )
    (net (code "60") (name "unconnected-(M1-PadD6)") (class "Default")
      (node (ref "M1") (pin "D6") (pinfunction "D6_D6") (pintype "bidirectional"))
    )
    (net (code "61") (name "unconnected-(M1-PadIOREF)") (class "Default")
      (node (ref "M1") (pin "IOREF") (pinfunction "IOREF_IOREF") (pintype "output"))
    )
    (net (code "62") (name "unconnected-(M1-PadRESERVED)") (class "Default")
      (node (ref "M1") (pin "RESERVED") (pinfunction "RESERVED_RESERVED") (pintype "no_connect"))
    )
    (net (code "63") (name "unconnected-(M1-PadSCL)") (class "Default")
      (node (ref "M1") (pin "SCL") (pinfunction "SCL_SCL") (pintype "bidirectional"))
    )
    (net (code "64") (name "unconnected-(M1-PadSDA)") (class "Default")
      (node (ref "M1") (pin "SDA") (pinfunction "SDA_SDA") (pintype "bidirectional"))
    )
    (net (code "65") (name "unconnected-(M1-RST-PadRESET_ICSP)") (class "Default")
      (node (ref "M1") (pin "RESET_ICSP") (pinfunction "RST_RESET_ICSP") (pintype "passive"))
    )
    (net (code "66") (name "unconnected-(M1-{slash}RESET-PadRESET)") (class "Default")
      (node (ref "M1") (pin "RESET") (pinfunction "/RESET_RESET") (pintype "bidirectional"))
    )
    (net (code "67") (name "unconnected-(U$3-DNC-Pad5)") (class "Default")
      (node (ref "U$3") (pin "5") (pinfunction "DNC_5") (pintype "bidirectional"))
    )
    (net (code "68") (name "unconnected-(U$3-DNC-Pad6)") (class "Default")
      (node (ref "U$3") (pin "6") (pinfunction "DNC_6") (pintype "bidirectional"))
    )
    (net (code "69") (name "unconnected-(U$3-DNC-Pad10)") (class "Default")
      (node (ref "U$3") (pin "10") (pinfunction "DNC_10") (pintype "bidirectional"))
    )
    (net (code "70") (name "unconnected-(U$3-DNC-Pad34)") (class "Default")
      (node (ref "U$3") (pin "34") (pinfunction "DNC_34") (pintype "bidirectional"))
    )
    (net (code "71") (name "unconnected-(U$3-DNC-Pad35)") (class "Default")
      (node (ref "U$3") (pin "35") (pinfunction "DNC_35") (pintype "bidirectional"))
    )
    (net (code "72") (name "unconnected-(U$3-RSVD-Pad9)") (class "Default")
      (node (ref "U$3") (pin "9") (pinfunction "RSVD_9") (pintype "bidirectional"))
    )
    (net (code "73") (name "unconnected-(U$6-N{slash}C-Pad2)") (class "Default")
      (node (ref "U$6") (pin "2") (pinfunction "N/C_2") (pintype "bidirectional"))
    )
    (net (code "74") (name "unconnected-(U$6-N{slash}C-Pad7)") (class "Default")
      (node (ref "U$6") (pin "7") (pinfunction "N/C_7") (pintype "bidirectional"))
    )
    (net (code "75") (name "unconnected-(X1-Pad1)") (class "Default")
      (node (ref "X1") (pin "1") (pinfunction "1_1") (pintype "passive"))
    )
    (net (code "76") (name "unconnected-(X1-Pad4)") (class "Default")
      (node (ref "X1") (pin "4") (pinfunction "4_4") (pintype "passive"))
    )
    (net (code "77") (name "unconnected-(X1-Pad6)") (class "Default")
      (node (ref "X1") (pin "6") (pinfunction "6_6") (pintype "passive"))
    )
    (net (code "78") (name "unconnected-(X1-Pad8)") (class "Default")
      (node (ref "X1") (pin "8") (pinfunction "8_8") (pintype "passive"))
    )
    (net (code "79") (name "~{ADC_RESET}") (class "Default")
      (node (ref "Q2") (pin "2") (pinfunction "S_2") (pintype "passive"))
      (node (ref "R31") (pin "2") (pinfunction "2_2") (pintype "passive"))
      (node (ref "R6") (pin "2") (pinfunction "2_2") (pintype "passive"))
      (node (ref "U$3") (pin "29") (pinfunction "~{RESET}_29") (pintype "bidirectional"))
    )
    (net (code "80") (name "~{AFE_PDN}") (class "Default")
      (node (ref "Q1") (pin "2") (pinfunction "S_2") (pintype "passive"))
      (node (ref "R1") (pin "2") (pinfunction "2_2") (pintype "passive"))
      (node (ref "U$3") (pin "20") (pinfunction "AFE_~{PDN}_20") (pintype "bidirectional"))
    )
    (net (code "81") (name "~{ARD_DRDY}") (class "Default")
      (node (ref "M1") (pin "D2") (pinfunction "D2_D2") (pintype "bidirectional"))
      (node (ref "Q3") (pin "3") (pinfunction "D_3") (pintype "passive"))
      (node (ref "R5") (pin "2") (pinfunction "2_2") (pintype "passive"))
    )
  )
)
